# communication-hub.net
KiCad netlist of a schematic drawn in EAGLE
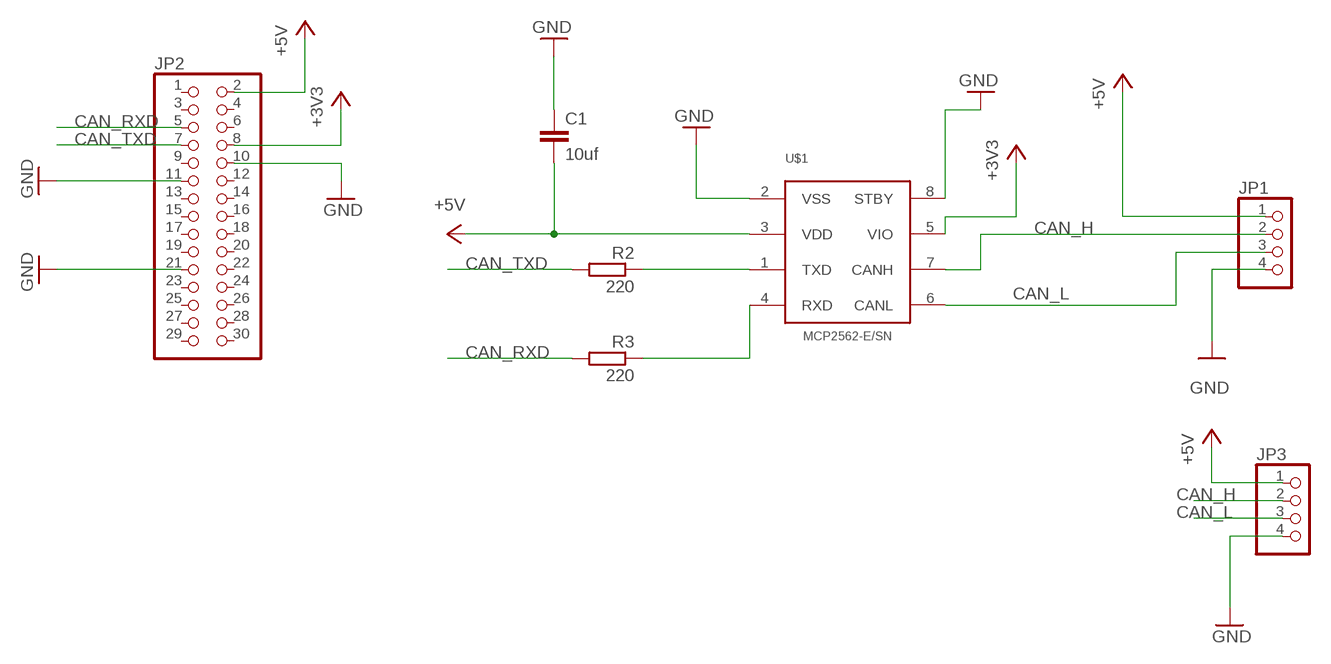
[diagram p0: schematic, sheet 1]

(export (version "E")
  (design (tool "Eeschema 10.0.6"))
  (components
    (comp (ref "C1")
      (value "10uf")
      (footprint "eagle-import:C0805")
      (libsource (lib "eagle-import") (part "C-EUC0805"))
    )
    (comp (ref "JP1")
      (value "PINHD-1X4")
      (footprint "eagle-import:1X04")
      (libsource (lib "eagle-import") (part "PINHD-1X4"))
    )
    (comp (ref "JP2")
      (value "PINHD-2X15")
      (footprint "eagle-import:2X15")
      (libsource (lib "eagle-import") (part "PINHD-2X15"))
    )
    (comp (ref "JP3")
      (value "PINHD-1X4")
      (footprint "eagle-import:1X04")
      (libsource (lib "eagle-import") (part "PINHD-1X4"))
    )
    (comp (ref "R2")
      (value "220")
      (footprint "eagle-import:R0805")
      (libsource (lib "eagle-import") (part "R-EU_R0805"))
    )
    (comp (ref "R3")
      (value "220")
      (footprint "eagle-import:R0805")
      (libsource (lib "eagle-import") (part "R-EU_R0805"))
    )
    (comp (ref "U$1")
      (value "MCP2562-E/SN")
      (footprint "eagle-import:SOIC8")
      (libsource (lib "eagle-import") (part "MCP2562-E/SN"))
    )
  )
  (nets
    (net (code "1") (name "+3V3") (class "Default")
      (node (ref "JP2") (pin "8") (pinfunction "8_8") (pintype "passive"))
      (node (ref "U$1") (pin "5") (pinfunction "VIO_5") (pintype "bidirectional"))
    )
    (net (code "2") (name "+5V") (class "Default")
      (node (ref "C1") (pin "2") (pinfunction "2_2") (pintype "passive"))
      (node (ref "JP1") (pin "1") (pinfunction "1_1") (pintype "passive"))
      (node (ref "JP2") (pin "2") (pinfunction "2_2") (pintype "passive"))
      (node (ref "JP3") (pin "1") (pinfunction "1_1") (pintype "passive"))
      (node (ref "U$1") (pin "3") (pinfunction "VDD_3") (pintype "bidirectional"))
    )
    (net (code "3") (name "/CAN_H") (class "Default")
      (node (ref "JP1") (pin "2") (pinfunction "2_2") (pintype "passive"))
      (node (ref "JP3") (pin "2") (pinfunction "2_2") (pintype "passive"))
      (node (ref "U$1") (pin "7") (pinfunction "CANH_7") (pintype "bidirectional"))
    )
    (net (code "4") (name "/CAN_L") (class "Default")
      (node (ref "JP1") (pin "3") (pinfunction "3_3") (pintype "passive"))
      (node (ref "JP3") (pin "3") (pinfunction "3_3") (pintype "passive"))
      (node (ref "U$1") (pin "6") (pinfunction "CANL_6") (pintype "bidirectional"))
    )
    (net (code "5") (name "/CAN_RXD") (class "Default")
      (node (ref "JP2") (pin "5") (pinfunction "5_5") (pintype "passive"))
      (node (ref "R3") (pin "2") (pinfunction "2_2") (pintype "passive"))
    )
    (net (code "6") (name "/CAN_TXD") (class "Default")
      (node (ref "JP2") (pin "7") (pinfunction "7_7") (pintype "passive"))
      (node (ref "R2") (pin "2") (pinfunction "2_2") (pintype "passive"))
    )
    (net (code "7") (name "GND") (class "Default")
      (node (ref "C1") (pin "1") (pinfunction "1_1") (pintype "passive"))
      (node (ref "JP1") (pin "4") (pinfunction "4_4") (pintype "passive"))
      (node (ref "JP2") (pin "10") (pinfunction "10_10") (pintype "passive"))
      (node (ref "JP2") (pin "11") (pinfunction "11_11") (pintype "passive"))
      (node (ref "JP2") (pin "21") (pinfunction "21_21") (pintype "passive"))
      (node (ref "JP3") (pin "4") (pinfunction "4_4") (pintype "passive"))
      (node (ref "U$1") (pin "2") (pinfunction "VSS_2") (pintype "bidirectional"))
      (node (ref "U$1") (pin "8") (pinfunction "STBY_8") (pintype "bidirectional"))
    )
    (net (code "8") (name "Net-(U$1-RXD)") (class "Default")
      (node (ref "R3") (pin "1") (pinfunction "1_1") (pintype "passive"))
      (node (ref "U$1") (pin "4") (pinfunction "RXD_4") (pintype "bidirectional"))
    )
    (net (code "9") (name "Net-(U$1-TXD)") (class "Default")
      (node (ref "R2") (pin "1") (pinfunction "1_1") (pintype "passive"))
      (node (ref "U$1") (pin "1") (pinfunction "TXD_1") (pintype "bidirectional"))
    )
    (net (code "10") (name "unconnected-(JP2-Pad1)") (class "Default")
      (node (ref "JP2") (pin "1") (pinfunction "1_1") (pintype "passive"))
    )
    (net (code "11") (name "unconnected-(JP2-Pad3)") (class "Default")
      (node (ref "JP2") (pin "3") (pinfunction "3_3") (pintype "passive"))
    )
    (net (code "12") (name "unconnected-(JP2-Pad4)") (class "Default")
      (node (ref "JP2") (pin "4") (pinfunction "4_4") (pintype "passive"))
    )
    (net (code "13") (name "unconnected-(JP2-Pad6)") (class "Default")
      (node (ref "JP2") (pin "6") (pinfunction "6_6") (pintype "passive"))
    )
    (net (code "14") (name "unconnected-(JP2-Pad9)") (class "Default")
      (node (ref "JP2") (pin "9") (pinfunction "9_9") (pintype "passive"))
    )
    (net (code "15") (name "unconnected-(JP2-Pad12)") (class "Default")
      (node (ref "JP2") (pin "12") (pinfunction "12_12") (pintype "passive"))
    )
    (net (code "16") (name "unconnected-(JP2-Pad13)") (class "Default")
      (node (ref "JP2") (pin "13") (pinfunction "13_13") (pintype "passive"))
    )
    (net (code "17") (name "unconnected-(JP2-Pad14)") (class "Default")
      (node (ref "JP2") (pin "14") (pinfunction "14_14") (pintype "passive"))
    )
    (net (code "18") (name "unconnected-(JP2-Pad15)") (class "Default")
      (node (ref "JP2") (pin "15") (pinfunction "15_15") (pintype "passive"))
    )
    (net (code "19") (name "unconnected-(JP2-Pad16)") (class "Default")
      (node (ref "JP2") (pin "16") (pinfunction "16_16") (pintype "passive"))
    )
    (net (code "20") (name "unconnected-(JP2-Pad17)") (class "Default")
      (node (ref "JP2") (pin "17") (pinfunction "17_17") (pintype "passive"))
    )
    (net (code "21") (name "unconnected-(JP2-Pad18)") (class "Default")
      (node (ref "JP2") (pin "18") (pinfunction "18_18") (pintype "passive"))
    )
    (net (code "22") (name "unconnected-(JP2-Pad19)") (class "Default")
      (node (ref "JP2") (pin "19") (pinfunction "19_19") (pintype "passive"))
    )
    (net (code "23") (name "unconnected-(JP2-Pad20)") (class "Default")
      (node (ref "JP2") (pin "20") (pinfunction "20_20") (pintype "passive"))
    )
    (net (code "24") (name "unconnected-(JP2-Pad22)") (class "Default")
      (node (ref "JP2") (pin "22") (pinfunction "22_22") (pintype "passive"))
    )
    (net (code "25") (name "unconnected-(JP2-Pad23)") (class "Default")
      (node (ref "JP2") (pin "23") (pinfunction "23_23") (pintype "passive"))
    )
    (net (code "26") (name "unconnected-(JP2-Pad24)") (class "Default")
      (node (ref "JP2") (pin "24") (pinfunction "24_24") (pintype "passive"))
    )
    (net (code "27") (name "unconnected-(JP2-Pad25)") (class "Default")
      (node (ref "JP2") (pin "25") (pinfunction "25_25") (pintype "passive"))
    )
    (net (code "28") (name "unconnected-(JP2-Pad26)") (class "Default")
      (node (ref "JP2") (pin "26") (pinfunction "26_26") (pintype "passive"))
    )
    (net (code "29") (name "unconnected-(JP2-Pad27)") (class "Default")
      (node (ref "JP2") (pin "27") (pinfunction "27_27") (pintype "passive"))
    )
    (net (code "30") (name "unconnected-(JP2-Pad28)") (class "Default")
      (node (ref "JP2") (pin "28") (pinfunction "28_28") (pintype "passive"))
    )
    (net (code "31") (name "unconnected-(JP2-Pad29)") (class "Default")
      (node (ref "JP2") (pin "29") (pinfunction "29_29") (pintype "passive"))
    )
    (net (code "32") (name "unconnected-(JP2-Pad30)") (class "Default")
      (node (ref "JP2") (pin "30") (pinfunction "30_30") (pintype "passive"))
    )
  )
)
